# LED_driver.net
KiCad netlist of a schematic drawn in Altium Designer
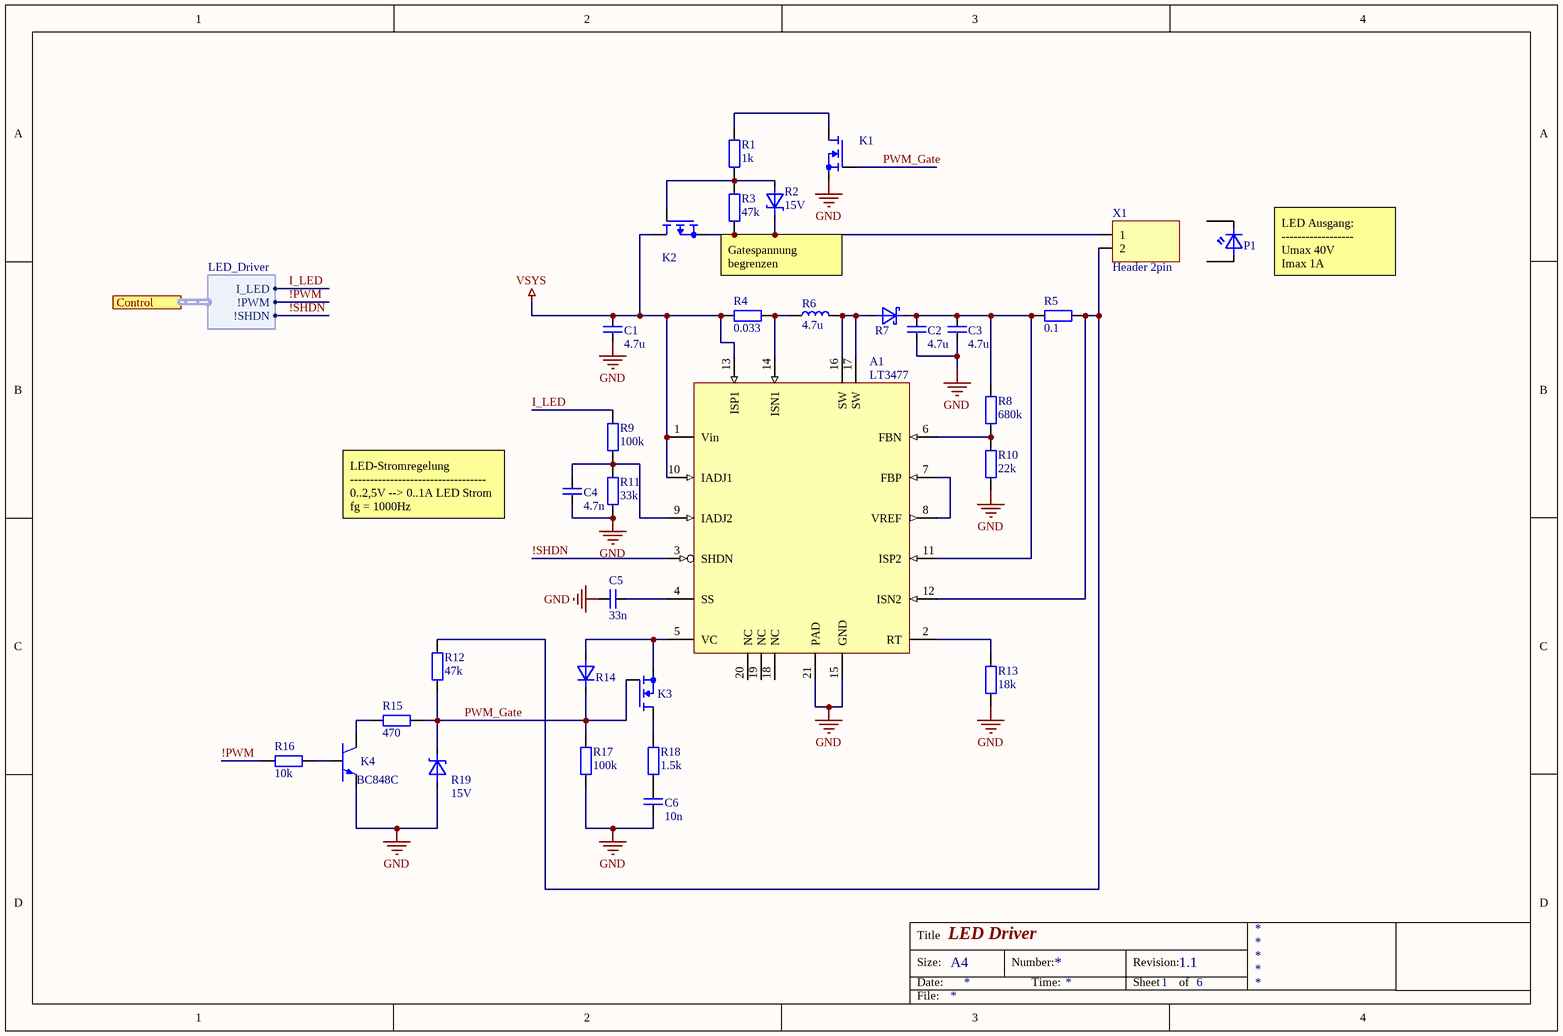
[diagram p0: LED_driver.SchDoc]

(export (version "E")
  (design (tool "Eeschema 10.0.6"))
  (components
    (comp (ref "A1")
      (value "LT3477")
      (footprint "TSSOP20 exposed pad")
      (description "3A, DC/DC Converter with Dual Rail-to-Rail Current Sense")
      (libsource (lib "IC") (part "LT3477"))
    )
    (comp (ref "C1") (value "4.7u") (footprint "1210") (libsource (lib "Passive") (part "Kondensator")))
    (comp (ref "C2") (value "4.7u") (footprint "1210") (libsource (lib "Passive") (part "Kondensator")))
    (comp (ref "C3") (value "4.7u") (footprint "1210") (libsource (lib "Passive") (part "Kondensator")))
    (comp (ref "C4") (value "4.7n") (footprint "0805") (libsource (lib "Passive") (part "Kondensator")))
    (comp (ref "C5") (value "33n") (footprint "0805") (libsource (lib "Passive") (part "Kondensator")))
    (comp (ref "C6") (value "10n") (footprint "0805") (libsource (lib "Passive") (part "Kondensator")))
    (comp (ref "K1")
      (value "MOSFET N-channel enh")
      (footprint "SOT23-3")
      (libsource (lib "Discrete_Semiconductors") (part "MOSFET N-channel enh"))
    )
    (comp (ref "K2")
      (value "pmos FDC658")
      (footprint "SuperSOT-6")
      (libsource (lib "Discrete_Semiconductors") (part "MOSFET P-channel enh"))
    )
    (comp (ref "K3")
      (value "MOSFET N-channel enh")
      (footprint "SOT23-3")
      (libsource (lib "Discrete_Semiconductors") (part "MOSFET N-channel enh"))
    )
    (comp (ref "K4")
      (value "BC848C")
      (footprint "SOT23-3")
      (libsource (lib "Discrete_Semiconductors") (part "Transistor NPN"))
    )
    (comp (ref "P1") (value "LED") (libsource (lib "Optoelectronics") (part "LED")))
    (comp (ref "R1") (value "1k") (footprint "0805") (libsource (lib "Passive") (part "Widerstand")))
    (comp (ref "R2")
      (value "15V")
      (footprint "SOD523")
      (libsource (lib "Discrete_Semiconductors") (part "Diode zener"))
    )
    (comp (ref "R3") (value "47k") (footprint "0805") (libsource (lib "Passive") (part "Widerstand")))
    (comp (ref "R4") (value "0.033") (footprint "2512") (libsource (lib "Passive") (part "Widerstand")))
    (comp (ref "R5") (value "0.1") (footprint "2512") (libsource (lib "Passive") (part "Widerstand")))
    (comp (ref "R6")
      (value "4.7u")
      (footprint "SMD_Ind_5x5")
      (libsource (lib "Passive") (part "Induktivität"))
    )
    (comp (ref "R7")
      (value "Diode shottky")
      (footprint "PowerDI123")
      (libsource (lib "Discrete_Semiconductors") (part "Diode shottky"))
    )
    (comp (ref "R8") (value "680k") (footprint "0805") (libsource (lib "Passive") (part "Widerstand")))
    (comp (ref "R9") (value "100k") (footprint "0805") (libsource (lib "Passive") (part "Widerstand")))
    (comp (ref "R10") (value "22k") (footprint "0805") (libsource (lib "Passive") (part "Widerstand")))
    (comp (ref "R11") (value "33k") (footprint "0805") (libsource (lib "Passive") (part "Widerstand")))
    (comp (ref "R12") (value "47k") (footprint "0805") (libsource (lib "Passive") (part "Widerstand")))
    (comp (ref "R13") (value "18k") (footprint "0805") (libsource (lib "Passive") (part "Widerstand")))
    (comp (ref "R14")
      (value "1N4148W")
      (footprint "SOD123F")
      (libsource (lib "Discrete_Semiconductors") (part "Diode"))
    )
    (comp (ref "R15") (value "470") (footprint "0805") (libsource (lib "Passive") (part "Widerstand")))
    (comp (ref "R16") (value "10k") (footprint "0805") (libsource (lib "Passive") (part "Widerstand")))
    (comp (ref "R17") (value "100k") (footprint "0805") (libsource (lib "Passive") (part "Widerstand")))
    (comp (ref "R18") (value "1.5k") (footprint "0805") (libsource (lib "Passive") (part "Widerstand")))
    (comp (ref "R19")
      (value "15V")
      (footprint "SOD523")
      (libsource (lib "Discrete_Semiconductors") (part "Diode zener"))
    )
    (comp (ref "X1")
      (value "Header 2pin")
      (footprint "PHOENIX_1729128")
      (libsource (lib "Connectors") (part "Header 2pin"))
    )
  )
  (nets
    (net (code "2") (name "/!PWM") (class "Default")
      (node (ref "R16") (pin "1") (pinfunction "1_1") (pintype "passive"))
    )
    (net (code "3") (name "/!SHDN") (class "Default")
      (node (ref "A1") (pin "3") (pinfunction "SHDN_3") (pintype "input"))
    )
    (net (code "4") (name "/I_LED") (class "Default")
      (node (ref "R9") (pin "2") (pinfunction "2_2") (pintype "passive"))
    )
    (net (code "5") (name "/PWM_Gate") (class "Default")
      (node (ref "K1") (pin "3") (pinfunction "Gate_3") (pintype "passive"))
      (node (ref "K3") (pin "3") (pinfunction "Gate_3") (pintype "passive"))
      (node (ref "R12") (pin "2") (pinfunction "2_2") (pintype "passive"))
      (node (ref "R14") (pin "1") (pinfunction "Kathode_1") (pintype "passive"))
      (node (ref "R15") (pin "2") (pinfunction "2_2") (pintype "passive"))
      (node (ref "R17") (pin "2") (pinfunction "2_2") (pintype "passive"))
      (node (ref "R19") (pin "1") (pinfunction "Kathode_1") (pintype "passive"))
    )
    (net (code "7") (name "GND") (class "Default")
      (node (ref "A1") (pin "15") (pinfunction "GND_15") (pintype "power_in"))
      (node (ref "A1") (pin "21") (pinfunction "PAD_21") (pintype "passive"))
      (node (ref "C1") (pin "1") (pinfunction "1_1") (pintype "passive"))
      (node (ref "C2") (pin "1") (pinfunction "1_1") (pintype "passive"))
      (node (ref "C3") (pin "1") (pinfunction "1_1") (pintype "passive"))
      (node (ref "C4") (pin "2") (pinfunction "2_2") (pintype "passive"))
      (node (ref "C5") (pin "2") (pinfunction "2_2") (pintype "passive"))
      (node (ref "C6") (pin "1") (pinfunction "1_1") (pintype "passive"))
      (node (ref "K1") (pin "2") (pinfunction "Source_2") (pintype "passive"))
      (node (ref "K4") (pin "2") (pinfunction "Emitter_2") (pintype "passive"))
      (node (ref "R10") (pin "1") (pinfunction "1_1") (pintype "passive"))
      (node (ref "R11") (pin "1") (pinfunction "1_1") (pintype "passive"))
      (node (ref "R13") (pin "1") (pinfunction "1_1") (pintype "passive"))
      (node (ref "R17") (pin "1") (pinfunction "1_1") (pintype "passive"))
      (node (ref "R19") (pin "2") (pinfunction "Annode_2") (pintype "passive"))
    )
    (net (code "8") (name "Net-(A1-FBN)") (class "Default")
      (node (ref "A1") (pin "6") (pinfunction "FBN_6") (pintype "input"))
      (node (ref "R10") (pin "2") (pinfunction "2_2") (pintype "passive"))
      (node (ref "R8") (pin "1") (pinfunction "1_1") (pintype "passive"))
    )
    (net (code "9") (name "Net-(A1-FBP)") (class "Default")
      (node (ref "A1") (pin "7") (pinfunction "FBP_7") (pintype "input"))
      (node (ref "A1") (pin "8") (pinfunction "VREF_8") (pintype "output"))
    )
    (net (code "10") (name "Net-(A1-IADJ2)") (class "Default")
      (node (ref "A1") (pin "9") (pinfunction "IADJ2_9") (pintype "input"))
      (node (ref "C4") (pin "1") (pinfunction "1_1") (pintype "passive"))
      (node (ref "R11") (pin "2") (pinfunction "2_2") (pintype "passive"))
      (node (ref "R9") (pin "1") (pinfunction "1_1") (pintype "passive"))
    )
    (net (code "11") (name "Net-(A1-ISN1)") (class "Default")
      (node (ref "A1") (pin "14") (pinfunction "ISN1_14") (pintype "input"))
      (node (ref "R4") (pin "2") (pinfunction "2_2") (pintype "passive"))
      (node (ref "R6") (pin "1") (pinfunction "1_1") (pintype "passive"))
    )
    (net (code "12") (name "Net-(A1-ISN2)") (class "Default")
      (node (ref "A1") (pin "12") (pinfunction "ISN2_12") (pintype "input"))
      (node (ref "R12") (pin "1") (pinfunction "1_1") (pintype "passive"))
      (node (ref "R5") (pin "2") (pinfunction "2_2") (pintype "passive"))
      (node (ref "X1") (pin "2") (pinfunction "2_2") (pintype "passive"))
    )
    (net (code "13") (name "Net-(A1-ISP2)") (class "Default")
      (node (ref "A1") (pin "11") (pinfunction "ISP2_11") (pintype "input"))
      (node (ref "C2") (pin "2") (pinfunction "2_2") (pintype "passive"))
      (node (ref "C3") (pin "2") (pinfunction "2_2") (pintype "passive"))
      (node (ref "R5") (pin "1") (pinfunction "1_1") (pintype "passive"))
      (node (ref "R7") (pin "1") (pinfunction "Kathode_1") (pintype "passive"))
      (node (ref "R8") (pin "2") (pinfunction "2_2") (pintype "passive"))
    )
    (net (code "14") (name "Net-(A1-RT)") (class "Default")
      (node (ref "A1") (pin "2") (pinfunction "RT_2") (pintype "passive"))
      (node (ref "R13") (pin "2") (pinfunction "2_2") (pintype "passive"))
    )
    (net (code "15") (name "Net-(A1-SS)") (class "Default")
      (node (ref "A1") (pin "4") (pinfunction "SS_4") (pintype "passive"))
      (node (ref "C5") (pin "1") (pinfunction "1_1") (pintype "passive"))
    )
    (net (code "16") (name "Net-(A1-VC)") (class "Default")
      (node (ref "A1") (pin "5") (pinfunction "VC_5") (pintype "passive"))
      (node (ref "K3") (pin "2") (pinfunction "Source_2") (pintype "passive"))
      (node (ref "R14") (pin "2") (pinfunction "Annode_2") (pintype "passive"))
    )
    (net (code "17") (name "Net-(C6-Pad2)") (class "Default")
      (node (ref "C6") (pin "2") (pinfunction "2_2") (pintype "passive"))
      (node (ref "R18") (pin "1") (pinfunction "1_1") (pintype "passive"))
    )
    (net (code "18") (name "Net-(K1-Drain)") (class "Default")
      (node (ref "K1") (pin "1") (pinfunction "Drain_1") (pintype "passive"))
      (node (ref "R1") (pin "2") (pinfunction "2_2") (pintype "passive"))
    )
    (net (code "19") (name "Net-(K2-Gate)") (class "Default")
      (node (ref "K2") (pin "3") (pinfunction "Gate_3") (pintype "passive"))
      (node (ref "R1") (pin "1") (pinfunction "1_1") (pintype "passive"))
      (node (ref "R2") (pin "2") (pinfunction "Annode_2") (pintype "passive"))
      (node (ref "R3") (pin "2") (pinfunction "2_2") (pintype "passive"))
    )
    (net (code "20") (name "Net-(K2-Source)") (class "Default")
      (node (ref "K2") (pin "2") (pinfunction "Source_2") (pintype "passive"))
      (node (ref "R2") (pin "1") (pinfunction "Kathode_1") (pintype "passive"))
      (node (ref "R3") (pin "1") (pinfunction "1_1") (pintype "passive"))
      (node (ref "X1") (pin "1") (pinfunction "1_1") (pintype "passive"))
    )
    (net (code "21") (name "Net-(K3-Drain)") (class "Default")
      (node (ref "K3") (pin "1") (pinfunction "Drain_1") (pintype "passive"))
      (node (ref "R18") (pin "2") (pinfunction "2_2") (pintype "passive"))
    )
    (net (code "22") (name "Net-(K4-Basis)") (class "Default")
      (node (ref "K4") (pin "3") (pinfunction "Basis_3") (pintype "passive"))
      (node (ref "R16") (pin "2") (pinfunction "2_2") (pintype "passive"))
    )
    (net (code "23") (name "Net-(K4-Collector)") (class "Default")
      (node (ref "K4") (pin "1") (pinfunction "Collector_1") (pintype "passive"))
      (node (ref "R15") (pin "1") (pinfunction "1_1") (pintype "passive"))
    )
    (net (code "24") (name "Net-(R7-Annode)") (class "Default")
      (node (ref "A1") (pin "16") (pinfunction "SW_16") (pintype "open_collector"))
      (node (ref "A1") (pin "17") (pinfunction "SW_17") (pintype "open_collector"))
      (node (ref "R6") (pin "2") (pinfunction "2_2") (pintype "passive"))
      (node (ref "R7") (pin "2") (pinfunction "Annode_2") (pintype "passive"))
    )
    (net (code "25") (name "VSYS") (class "Default")
      (node (ref "A1") (pin "1") (pinfunction "Vin_1") (pintype "power_in"))
      (node (ref "A1") (pin "10") (pinfunction "IADJ1_10") (pintype "input"))
      (node (ref "A1") (pin "13") (pinfunction "ISP1_13") (pintype "input"))
      (node (ref "C1") (pin "2") (pinfunction "2_2") (pintype "passive"))
      (node (ref "K2") (pin "1") (pinfunction "Drain_1") (pintype "passive"))
      (node (ref "R4") (pin "1") (pinfunction "1_1") (pintype "passive"))
    )
    (net (code "26") (name "unconnected-(A1-NC-Pad18)") (class "Default")
      (node (ref "A1") (pin "18") (pinfunction "NC_18") (pintype "passive"))
    )
    (net (code "27") (name "unconnected-(A1-NC-Pad19)") (class "Default")
      (node (ref "A1") (pin "19") (pinfunction "NC_19") (pintype "passive"))
    )
    (net (code "28") (name "unconnected-(A1-NC-Pad20)") (class "Default")
      (node (ref "A1") (pin "20") (pinfunction "NC_20") (pintype "passive"))
    )
    (net (code "29") (name "unconnected-(P1-Annode-Pad2)") (class "Default")
      (node (ref "P1") (pin "2") (pinfunction "Annode_2") (pintype "passive"))
    )
    (net (code "30") (name "unconnected-(P1-Kathode-Pad1)") (class "Default")
      (node (ref "P1") (pin "1") (pinfunction "Kathode_1") (pintype "passive"))
    )
  )
)
